# chibarobo2024.net
KiCad netlist of a schematic drawn in EAGLE
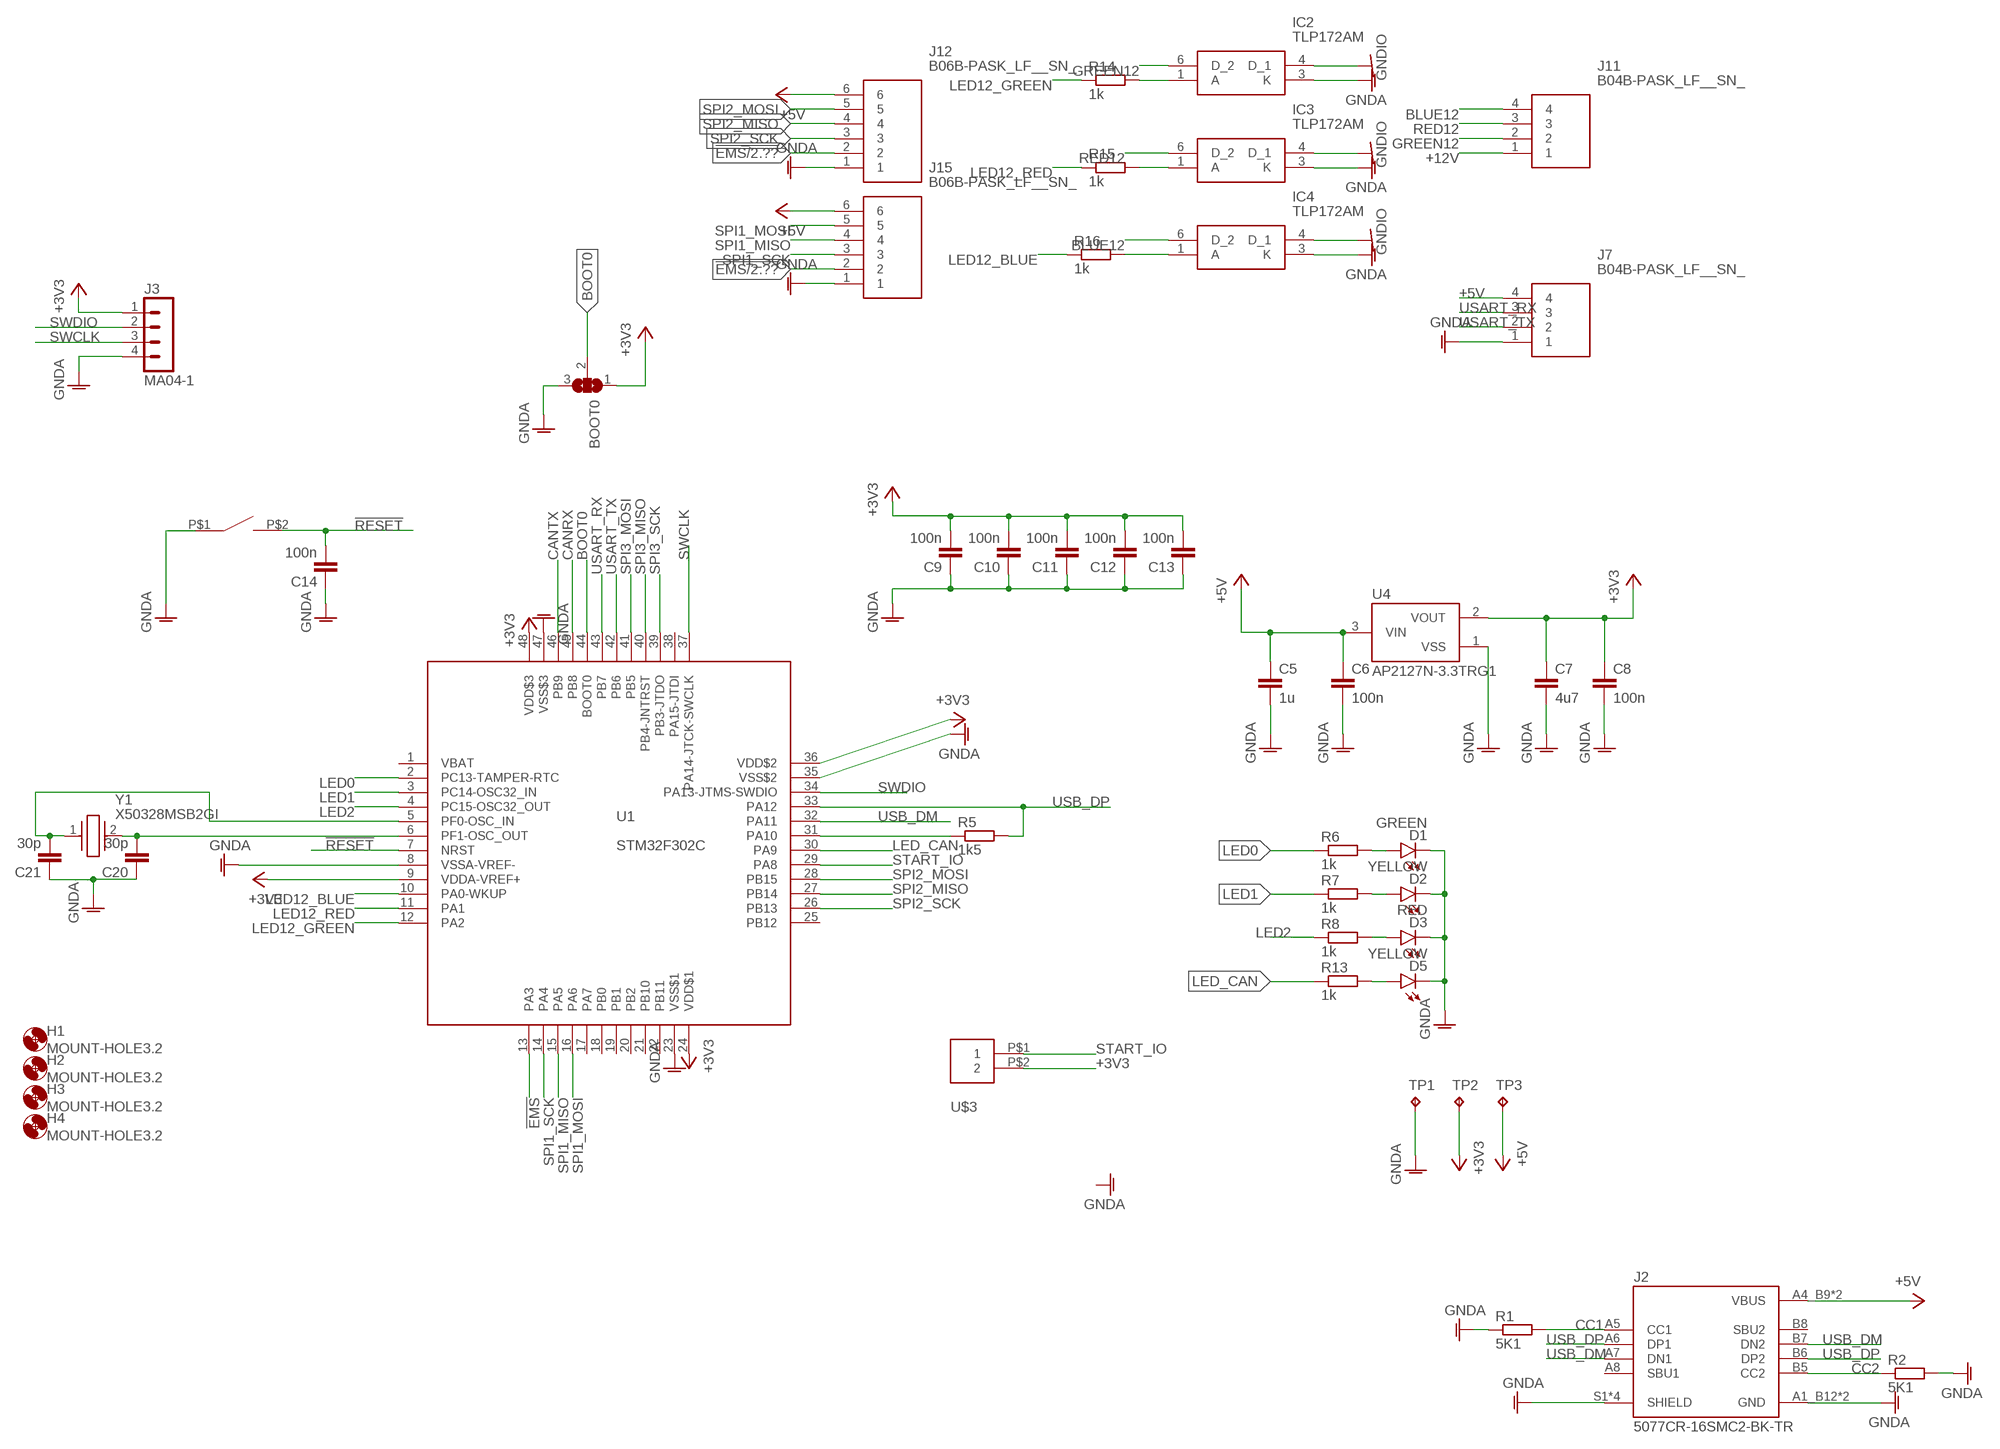
[diagram p0: schematic, sheet 1]
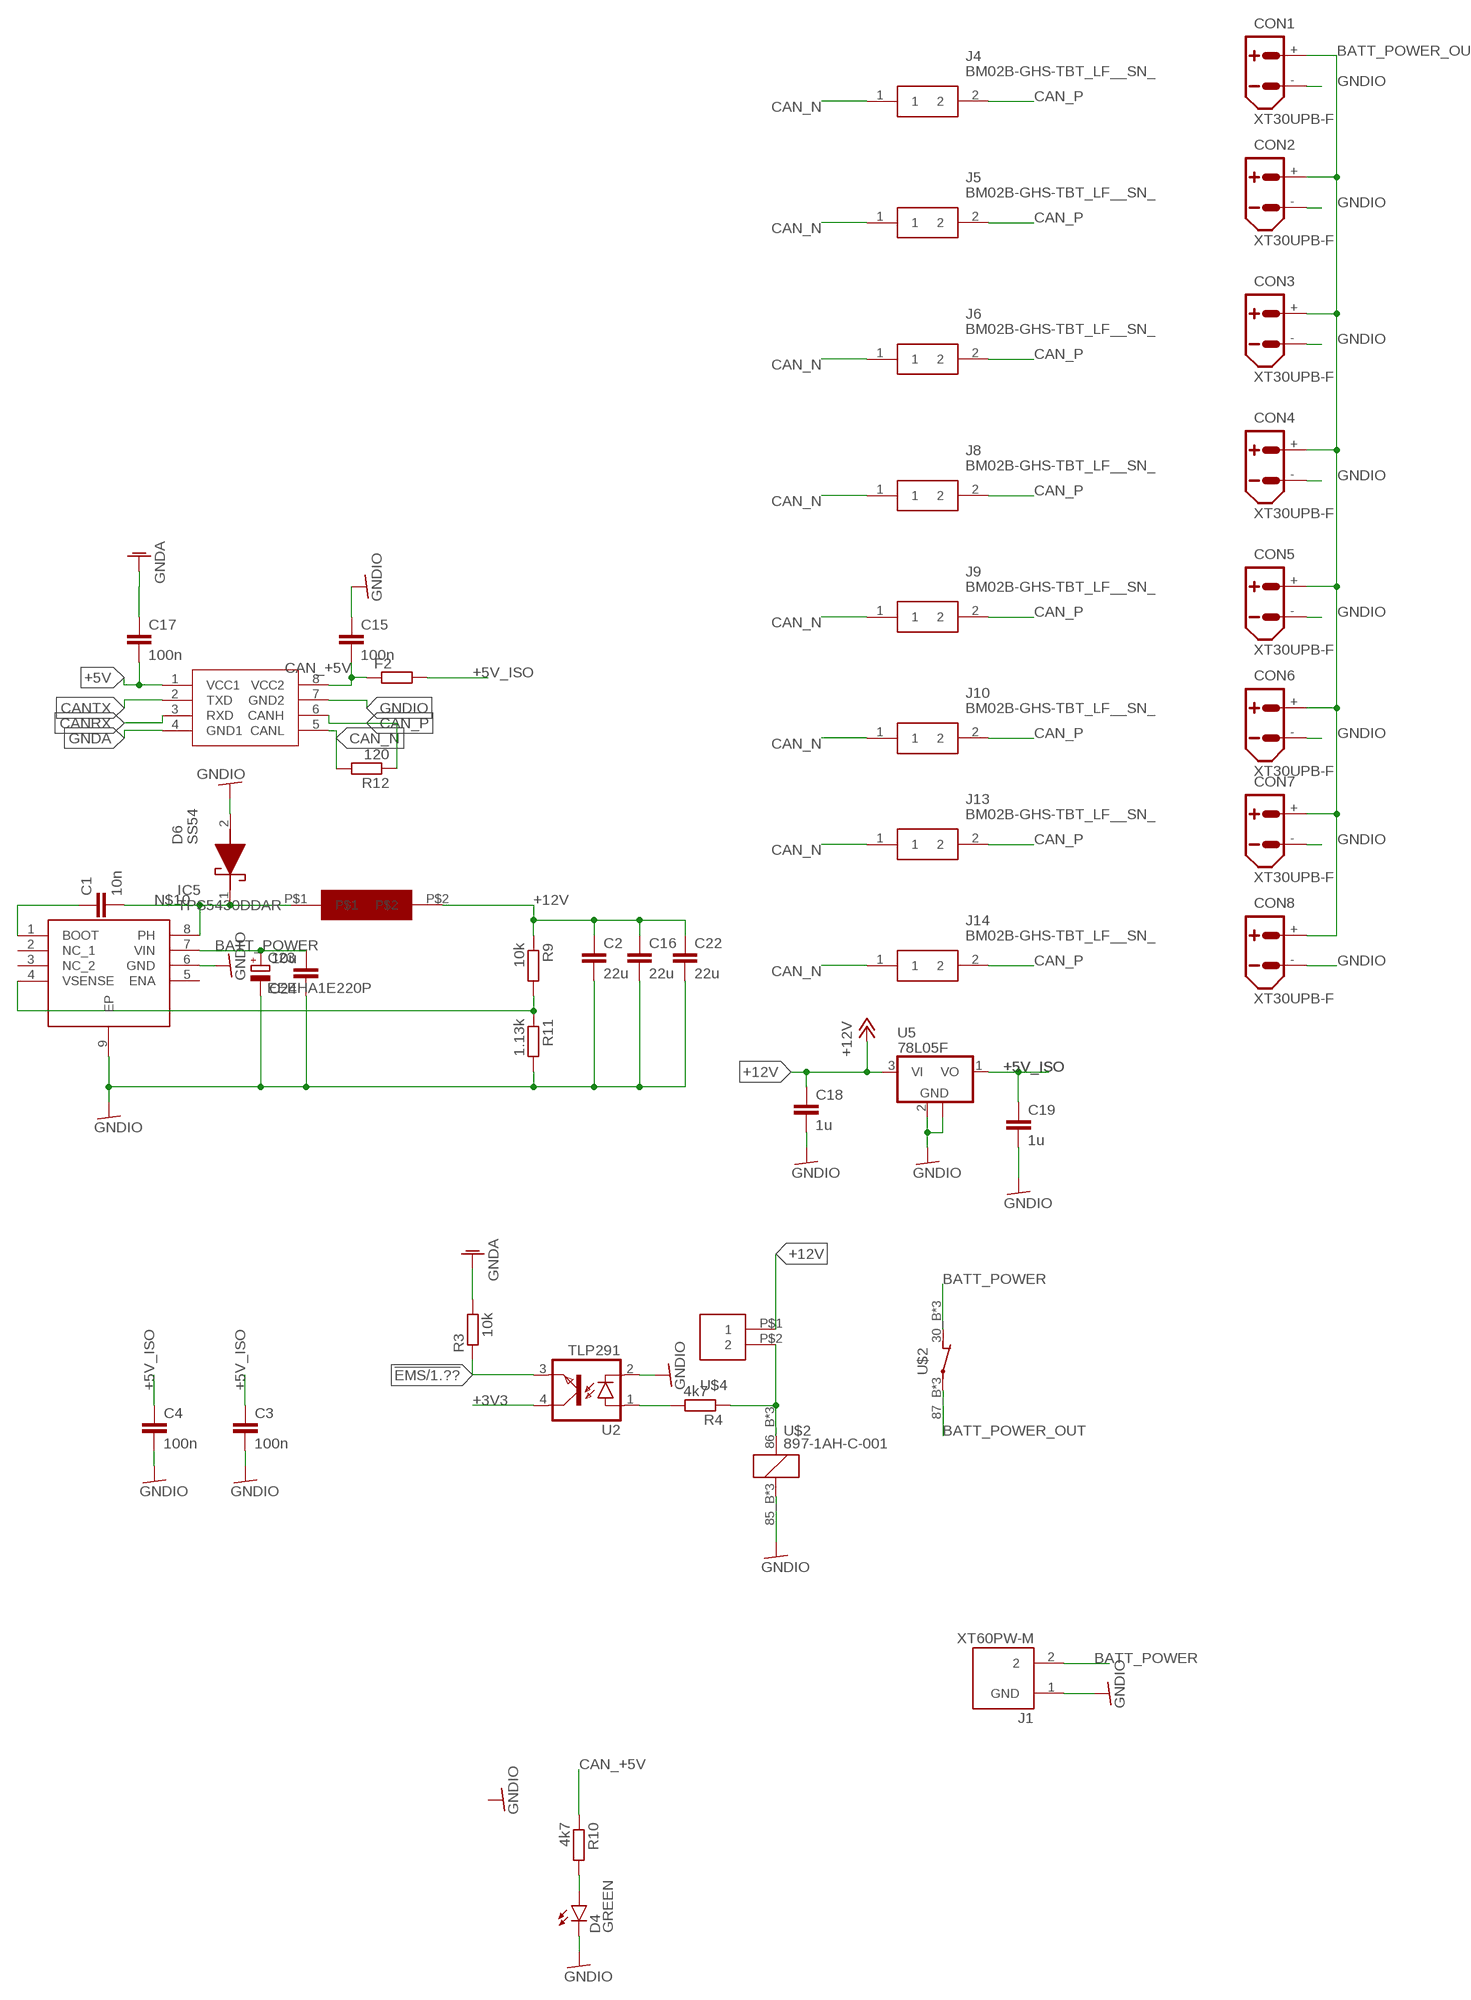
[diagram p1: schematic, sheet 2]

(export (version "E")
  (design (tool "Eeschema 10.0.6"))
  (components
    (comp (ref "BOOT0")
      (value "SJ2W")
      (footprint "eagle-import:SJ_2")
      (libsource (lib "eagle-import") (part "SJ2W"))
    )
    (comp (ref "C5")
      (value "1u")
      (footprint "eagle-import:C0603")
      (libsource (lib "eagle-import") (part "C-EUC0603"))
    )
    (comp (ref "C6")
      (value "100n")
      (footprint "eagle-import:C0603")
      (libsource (lib "eagle-import") (part "C-EUC0603"))
    )
    (comp (ref "C7")
      (value "4u7")
      (footprint "eagle-import:C0805")
      (libsource (lib "eagle-import") (part "C-EUC0805"))
    )
    (comp (ref "C8")
      (value "100n")
      (footprint "eagle-import:C0603")
      (libsource (lib "eagle-import") (part "C-EUC0603"))
    )
    (comp (ref "C9")
      (value "100n")
      (footprint "eagle-import:C0603")
      (libsource (lib "eagle-import") (part "C-EUC0603"))
    )
    (comp (ref "C10")
      (value "100n")
      (footprint "eagle-import:C0603")
      (libsource (lib "eagle-import") (part "C-EUC0603"))
    )
    (comp (ref "C11")
      (value "100n")
      (footprint "eagle-import:C0603")
      (libsource (lib "eagle-import") (part "C-EUC0603"))
    )
    (comp (ref "C12")
      (value "100n")
      (footprint "eagle-import:C0603")
      (libsource (lib "eagle-import") (part "C-EUC0603"))
    )
    (comp (ref "C13")
      (value "100n")
      (footprint "eagle-import:C0603")
      (libsource (lib "eagle-import") (part "C-EUC0603"))
    )
    (comp (ref "C14")
      (value "100n")
      (footprint "eagle-import:C0603")
      (libsource (lib "eagle-import") (part "C-EUC0603"))
    )
    (comp (ref "C20")
      (value "30p")
      (footprint "eagle-import:C0603")
      (libsource (lib "eagle-import") (part "C-EUC0603"))
    )
    (comp (ref "C21")
      (value "30p")
      (footprint "eagle-import:C0603")
      (libsource (lib "eagle-import") (part "C-EUC0603"))
    )
    (comp (ref "D1")
      (value "GREEN")
      (footprint "eagle-import:CHIPLED_0805")
      (libsource (lib "eagle-import") (part "LEDCHIPLED_0805"))
    )
    (comp (ref "D2")
      (value "YELLOW")
      (footprint "eagle-import:CHIPLED_0805")
      (libsource (lib "eagle-import") (part "LEDCHIPLED_0805"))
    )
    (comp (ref "D3")
      (value "RED")
      (footprint "eagle-import:CHIPLED_0805")
      (libsource (lib "eagle-import") (part "LEDCHIPLED_0805"))
    )
    (comp (ref "D5")
      (value "YELLOW")
      (footprint "eagle-import:CHIPLED_0805")
      (libsource (lib "eagle-import") (part "LEDCHIPLED_0805"))
    )
    (comp (ref "H1")
      (value "MOUNT-HOLE3.2")
      (footprint "eagle-import:3,2")
      (libsource (lib "eagle-import") (part "MOUNT-HOLE3.2"))
    )
    (comp (ref "H2")
      (value "MOUNT-HOLE3.2")
      (footprint "eagle-import:3,2")
      (libsource (lib "eagle-import") (part "MOUNT-HOLE3.2"))
    )
    (comp (ref "H3")
      (value "MOUNT-HOLE3.2")
      (footprint "eagle-import:3,2")
      (libsource (lib "eagle-import") (part "MOUNT-HOLE3.2"))
    )
    (comp (ref "H4")
      (value "MOUNT-HOLE3.2")
      (footprint "eagle-import:3,2")
      (libsource (lib "eagle-import") (part "MOUNT-HOLE3.2"))
    )
    (comp (ref "IC2")
      (value "TLP172AM")
      (footprint "eagle-import:11-4M1S")
      (libsource (lib "eagle-import") (part "TLP172AM"))
    )
    (comp (ref "IC3")
      (value "TLP172AM")
      (footprint "eagle-import:11-4M1S")
      (libsource (lib "eagle-import") (part "TLP172AM"))
    )
    (comp (ref "IC4")
      (value "TLP172AM")
      (footprint "eagle-import:11-4M1S")
      (libsource (lib "eagle-import") (part "TLP172AM"))
    )
    (comp (ref "J2")
      (value "5077CR-16SMC2-BK-TR")
      (footprint "eagle-import:NELTRON_5077CR-16SMC2-BK-TR")
      (fields (field (name "MF") "Neltron"))
      (libsource (lib "eagle-import") (part "5077CR-16SMC2-BK-TR"))
    )
    (comp (ref "J3")
      (value "MA04-1")
      (footprint "eagle-import:MA04-1")
      (libsource (lib "eagle-import") (part "MA04-1"))
    )
    (comp (ref "J7")
      (value "B04B-PASK_LF__SN_")
      (footprint "eagle-import:B04BPASKLFSN")
      (fields (field (name "ARROW_PART_NUMBER") "B04B-PASK(LF)(SN)"))
      (libsource (lib "eagle-import") (part "B04B-PASK_LF__SN_"))
    )
    (comp (ref "J11")
      (value "B04B-PASK_LF__SN_")
      (footprint "eagle-import:B04BPASKLFSN")
      (fields (field (name "ARROW_PART_NUMBER") "B04B-PASK(LF)(SN)"))
      (libsource (lib "eagle-import") (part "B04B-PASK_LF__SN_"))
    )
    (comp (ref "J12")
      (value "B06B-PASK_LF__SN_")
      (footprint "eagle-import:B06BPASKLFSN")
      (fields
        (field (name "ARROW_PART_NUMBER") "B06B-PASK(LF)(SN)")
        (field (name "MOUSER_PART_NUMBER") "306-B06BPASKLFSN")
      )
      (libsource (lib "eagle-import") (part "B06B-PASK_LF__SN_"))
    )
    (comp (ref "J15")
      (value "B06B-PASK_LF__SN_")
      (footprint "eagle-import:B06BPASKLFSN")
      (fields
        (field (name "ARROW_PART_NUMBER") "B06B-PASK(LF)(SN)")
        (field (name "MOUSER_PART_NUMBER") "306-B06BPASKLFSN")
      )
      (libsource (lib "eagle-import") (part "B06B-PASK_LF__SN_"))
    )
    (comp (ref "R1")
      (value "5K1")
      (footprint "eagle-import:R0603")
      (libsource (lib "eagle-import") (part "R-EU_R0603"))
    )
    (comp (ref "R2")
      (value "5K1")
      (footprint "eagle-import:R0603")
      (libsource (lib "eagle-import") (part "R-EU_R0603"))
    )
    (comp (ref "R5")
      (value "1k5")
      (footprint "eagle-import:R0603")
      (libsource (lib "eagle-import") (part "R-EU_R0603"))
    )
    (comp (ref "R6")
      (value "1k")
      (footprint "eagle-import:R0603")
      (libsource (lib "eagle-import") (part "R-EU_R0603"))
    )
    (comp (ref "R7")
      (value "1k")
      (footprint "eagle-import:R0603")
      (libsource (lib "eagle-import") (part "R-EU_R0603"))
    )
    (comp (ref "R8")
      (value "1k")
      (footprint "eagle-import:R0603")
      (libsource (lib "eagle-import") (part "R-EU_R0603"))
    )
    (comp (ref "R13")
      (value "1k")
      (footprint "eagle-import:R0603")
      (libsource (lib "eagle-import") (part "R-EU_R0603"))
    )
    (comp (ref "R14")
      (value "1k")
      (footprint "eagle-import:R0603")
      (libsource (lib "eagle-import") (part "R-EU_R0603"))
    )
    (comp (ref "R15")
      (value "1k")
      (footprint "eagle-import:R0603")
      (libsource (lib "eagle-import") (part "R-EU_R0603"))
    )
    (comp (ref "R16")
      (value "1k")
      (footprint "eagle-import:R0603")
      (libsource (lib "eagle-import") (part "R-EU_R0603"))
    )
    (comp (ref "S1")
      (value "SWITCH_TACTILETOP")
      (footprint "eagle-import:SWITCH_TACTILE_3X6")
      (libsource (lib "eagle-import") (part "SWITCH_TACTILETOP"))
    )
    (comp (ref "TP1")
      (value "TPB1,27")
      (footprint "eagle-import:B1,27")
      (libsource (lib "eagle-import") (part "TPB1,27"))
    )
    (comp (ref "TP2")
      (value "TPB1,27")
      (footprint "eagle-import:B1,27")
      (libsource (lib "eagle-import") (part "TPB1,27"))
    )
    (comp (ref "TP3")
      (value "TPB1,27")
      (footprint "eagle-import:B1,27")
      (libsource (lib "eagle-import") (part "TPB1,27"))
    )
    (comp (ref "U$3")
      (value "XH-2-STRAIGHT")
      (footprint "eagle-import:CON-XH-2-STRAIGHT")
      (libsource (lib "eagle-import") (part "XH-2-STRAIGHT"))
    )
    (comp (ref "U1")
      (value "STM32F302C")
      (footprint "eagle-import:LQFP48")
      (libsource (lib "eagle-import") (part "STM32F303C"))
    )
    (comp (ref "U4")
      (value "AP2127N-3.3TRG1")
      (footprint "eagle-import:SOT95P240X110-3")
      (libsource (lib "eagle-import") (part "XC6206"))
    )
    (comp (ref "Y1")
      (value "X50328MSB2GI")
      (footprint "eagle-import:RESC5032X135N")
      (libsource (lib "eagle-import") (part "X50328MSB2GI"))
    )
    (comp (ref "C1")
      (value "10n")
      (footprint "eagle-import:C0603")
      (libsource (lib "eagle-import") (part "rcl_334_C-EUC0603"))
    )
    (comp (ref "C2")
      (value "22u")
      (footprint "eagle-import:C0805")
      (libsource (lib "eagle-import") (part "rcl_334_C-EUC0805"))
    )
    (comp (ref "C3")
      (value "100n")
      (footprint "eagle-import:C0603")
      (libsource (lib "eagle-import") (part "rcl_334_C-EUC0603"))
    )
    (comp (ref "C4")
      (value "100n")
      (footprint "eagle-import:C0603")
      (libsource (lib "eagle-import") (part "rcl_334_C-EUC0603"))
    )
    (comp (ref "C15")
      (value "100n")
      (footprint "eagle-import:C0603")
      (libsource (lib "eagle-import") (part "rcl_334_C-EUC0603"))
    )
    (comp (ref "C16")
      (value "22u")
      (footprint "eagle-import:C0805")
      (libsource (lib "eagle-import") (part "rcl_334_C-EUC0805"))
    )
    (comp (ref "C17")
      (value "100n")
      (footprint "eagle-import:C0603")
      (libsource (lib "eagle-import") (part "rcl_334_C-EUC0603"))
    )
    (comp (ref "C18")
      (value "1u")
      (footprint "eagle-import:C0603")
      (libsource (lib "eagle-import") (part "C-EUC0603"))
    )
    (comp (ref "C19")
      (value "1u")
      (footprint "eagle-import:C0603")
      (libsource (lib "eagle-import") (part "C-EUC0603"))
    )
    (comp (ref "C22")
      (value "22u")
      (footprint "eagle-import:C0805")
      (libsource (lib "eagle-import") (part "rcl_334_C-EUC0805"))
    )
    (comp (ref "C23")
      (value "EEEHA1E220P")
      (footprint "eagle-import:153CLV-0605")
      (libsource (lib "eagle-import") (part "CPOL-EU153CLV-0605"))
    )
    (comp (ref "C24")
      (value "10u")
      (footprint "eagle-import:C1210")
      (libsource (lib "eagle-import") (part "rcl_334_C-EUC1210"))
    )
    (comp (ref "CON1")
      (value "XT30UPB-F")
      (footprint "eagle-import:XT30UPB-F")
      (libsource (lib "eagle-import") (part "XT30UPB-F"))
    )
    (comp (ref "CON2")
      (value "XT30UPB-F")
      (footprint "eagle-import:XT30UPB-F")
      (libsource (lib "eagle-import") (part "XT30UPB-F"))
    )
    (comp (ref "CON3")
      (value "XT30UPB-F")
      (footprint "eagle-import:XT30UPB-F")
      (libsource (lib "eagle-import") (part "XT30UPB-F"))
    )
    (comp (ref "CON4")
      (value "XT30UPB-F")
      (footprint "eagle-import:XT30UPB-F")
      (libsource (lib "eagle-import") (part "XT30UPB-F"))
    )
    (comp (ref "CON5")
      (value "XT30UPB-F")
      (footprint "eagle-import:XT30UPB-F")
      (libsource (lib "eagle-import") (part "XT30UPB-F"))
    )
    (comp (ref "CON6")
      (value "XT30UPB-F")
      (footprint "eagle-import:XT30UPB-F")
      (libsource (lib "eagle-import") (part "XT30UPB-F"))
    )
    (comp (ref "CON7")
      (value "XT30UPB-F")
      (footprint "eagle-import:XT30UPB-F")
      (libsource (lib "eagle-import") (part "XT30UPB-F"))
    )
    (comp (ref "CON8")
      (value "XT30UPB-F")
      (footprint "eagle-import:XT30UPB-F")
      (libsource (lib "eagle-import") (part "XT30UPB-F"))
    )
    (comp (ref "D4")
      (value "GREEN")
      (footprint "eagle-import:CHIPLED_0805")
      (libsource (lib "eagle-import") (part "LEDCHIPLED_0805"))
    )
    (comp (ref "D6")
      (value "SS54")
      (footprint "eagle-import:DIOM5126X245N")
      (libsource (lib "eagle-import") (part "SS54"))
    )
    (comp (ref "F2")
      (value "R-EU_R1206")
      (footprint "eagle-import:R1206")
      (libsource (lib "eagle-import") (part "R-EU_R1206"))
    )
    (comp (ref "IC5")
      (value "TPS5430DDAR")
      (footprint "eagle-import:SOIC127P600X170-9N")
      (libsource (lib "eagle-import") (part "TPS5430DDAR"))
    )
    (comp (ref "J1")
      (value "XT60PW-M")
      (footprint "eagle-import:AMASS_XT60PW-M")
      (fields (field (name "MF") "AMASS") (field (name "MP") "XT60PW-M "))
      (libsource (lib "eagle-import") (part "XT60PW-M"))
    )
    (comp (ref "J4")
      (value "BM02B-GHS-TBT_LF__SN_")
      (footprint "eagle-import:BM02B-GHS-TBT_1")
      (fields (field (name "MANUFACTURER_PART_NUMBER") "BM02B-GHS-TBT(LF)(SN)"))
      (libsource (lib "eagle-import") (part "BM02B-GHS-TBT_LF__SN_"))
    )
    (comp (ref "J5")
      (value "BM02B-GHS-TBT_LF__SN_")
      (footprint "eagle-import:BM02B-GHS-TBT_1")
      (fields (field (name "MANUFACTURER_PART_NUMBER") "BM02B-GHS-TBT(LF)(SN)"))
      (libsource (lib "eagle-import") (part "BM02B-GHS-TBT_LF__SN_"))
    )
    (comp (ref "J6")
      (value "BM02B-GHS-TBT_LF__SN_")
      (footprint "eagle-import:BM02B-GHS-TBT_1")
      (fields (field (name "MANUFACTURER_PART_NUMBER") "BM02B-GHS-TBT(LF)(SN)"))
      (libsource (lib "eagle-import") (part "BM02B-GHS-TBT_LF__SN_"))
    )
    (comp (ref "J8")
      (value "BM02B-GHS-TBT_LF__SN_")
      (footprint "eagle-import:BM02B-GHS-TBT_1")
      (fields (field (name "MANUFACTURER_PART_NUMBER") "BM02B-GHS-TBT(LF)(SN)"))
      (libsource (lib "eagle-import") (part "BM02B-GHS-TBT_LF__SN_"))
    )
    (comp (ref "J9")
      (value "BM02B-GHS-TBT_LF__SN_")
      (footprint "eagle-import:BM02B-GHS-TBT_1")
      (fields (field (name "MANUFACTURER_PART_NUMBER") "BM02B-GHS-TBT(LF)(SN)"))
      (libsource (lib "eagle-import") (part "BM02B-GHS-TBT_LF__SN_"))
    )
    (comp (ref "J10")
      (value "BM02B-GHS-TBT_LF__SN_")
      (footprint "eagle-import:BM02B-GHS-TBT_1")
      (fields (field (name "MANUFACTURER_PART_NUMBER") "BM02B-GHS-TBT(LF)(SN)"))
      (libsource (lib "eagle-import") (part "BM02B-GHS-TBT_LF__SN_"))
    )
    (comp (ref "J13")
      (value "BM02B-GHS-TBT_LF__SN_")
      (footprint "eagle-import:BM02B-GHS-TBT_1")
      (fields (field (name "MANUFACTURER_PART_NUMBER") "BM02B-GHS-TBT(LF)(SN)"))
      (libsource (lib "eagle-import") (part "BM02B-GHS-TBT_LF__SN_"))
    )
    (comp (ref "J14")
      (value "BM02B-GHS-TBT_LF__SN_")
      (footprint "eagle-import:BM02B-GHS-TBT_1")
      (fields (field (name "MANUFACTURER_PART_NUMBER") "BM02B-GHS-TBT(LF)(SN)"))
      (libsource (lib "eagle-import") (part "BM02B-GHS-TBT_LF__SN_"))
    )
    (comp (ref "R3")
      (value "10k")
      (footprint "eagle-import:R0603")
      (libsource (lib "eagle-import") (part "R-EU_R0603"))
    )
    (comp (ref "R4")
      (value "4k7")
      (footprint "eagle-import:R0603")
      (libsource (lib "eagle-import") (part "R-EU_R0603"))
    )
    (comp (ref "R9")
      (value "10k")
      (footprint "eagle-import:R0603")
      (libsource (lib "eagle-import") (part "rcl_334_R-EU_R0603"))
    )
    (comp (ref "R10")
      (value "4k7")
      (footprint "eagle-import:R0603")
      (libsource (lib "eagle-import") (part "R-EU_R0603"))
    )
    (comp (ref "R11")
      (value "1.13k")
      (footprint "eagle-import:R0603")
      (libsource (lib "eagle-import") (part "rcl_334_R-EU_R0603"))
    )
    (comp (ref "R12")
      (value "120")
      (footprint "eagle-import:R0603")
      (libsource (lib "eagle-import") (part "rcl_334_R-EU_R0603"))
    )
    (comp (ref "U$1")
      (value "CA-IS1044S")
      (footprint "eagle-import:SOIC8")
      (libsource (lib "eagle-import") (part "CA-IS1044S"))
    )
    (comp (ref "U$2")
      (value "897-1AH-C-001")
      (footprint "eagle-import:897-1AH-C-001")
      (libsource (lib "eagle-import") (part "897-1AH-C-001"))
    )
    (comp (ref "U$4")
      (value "XH-2-STRAIGHT")
      (footprint "eagle-import:CON-XH-2-STRAIGHT")
      (libsource (lib "eagle-import") (part "XH-2-STRAIGHT"))
    )
    (comp (ref "U$5")
      (value "INDUCTOR125_125")
      (footprint "eagle-import:INDUCTOR125_125")
      (libsource (lib "eagle-import") (part "INDUCTOR125_125"))
    )
    (comp (ref "U2")
      (value "TLP291")
      (footprint "eagle-import:MINI-FLAT-4")
      (libsource (lib "eagle-import") (part "TLP291"))
    )
    (comp (ref "U5")
      (value "78L05F")
      (footprint "eagle-import:SOT89")
      (libsource (lib "eagle-import") (part "78LF05"))
    )
  )
  (nets
    (net (code "1") (name "+3V3") (class "Default")
      (node (ref "BOOT0") (pin "1") (pinfunction "1_1") (pintype "passive"))
      (node (ref "C10") (pin "2") (pinfunction "2_2") (pintype "passive"))
      (node (ref "C11") (pin "2") (pinfunction "2_2") (pintype "passive"))
      (node (ref "C12") (pin "2") (pinfunction "2_2") (pintype "passive"))
      (node (ref "C13") (pin "2") (pinfunction "2_2") (pintype "passive"))
      (node (ref "C7") (pin "1") (pinfunction "1_1") (pintype "passive"))
      (node (ref "C8") (pin "1") (pinfunction "1_1") (pintype "passive"))
      (node (ref "C9") (pin "2") (pinfunction "2_2") (pintype "passive"))
      (node (ref "J3") (pin "1") (pinfunction "1_1") (pintype "passive"))
      (node (ref "TP2") (pin "TP") (pinfunction "TP_TP") (pintype "input"))
      (node (ref "U$3") (pin "P$2") (pinfunction "2_P$2") (pintype "bidirectional"))
      (node (ref "U1") (pin "24") (pinfunction "VDD$1_24") (pintype "passive"))
      (node (ref "U1") (pin "36") (pinfunction "VDD$2_36") (pintype "passive"))
      (node (ref "U1") (pin "48") (pinfunction "VDD$3_48") (pintype "passive"))
      (node (ref "U1") (pin "9") (pinfunction "VDDA-VREF+_9") (pintype "bidirectional"))
      (node (ref "U2") (pin "4") (pinfunction "COL_4") (pintype "passive"))
      (node (ref "U4") (pin "2") (pinfunction "VOUT_2") (pintype "bidirectional"))
    )
    (net (code "2") (name "+5V") (class "Default")
      (node (ref "C17") (pin "2") (pinfunction "2_2") (pintype "passive"))
      (node (ref "C5") (pin "1") (pinfunction "1_1") (pintype "passive"))
      (node (ref "C6") (pin "1") (pinfunction "1_1") (pintype "passive"))
      (node (ref "J12") (pin "6") (pinfunction "6_6") (pintype "bidirectional"))
      (node (ref "J15") (pin "6") (pinfunction "6_6") (pintype "bidirectional"))
      (node (ref "J2") (pin "A4_B9") (pinfunction "VBUS_A4_B9") (pintype "power_in"))
      (node (ref "J2") (pin "B4_A9") (pinfunction "VBUS_B4_A9") (pintype "power_in"))
      (node (ref "J7") (pin "4") (pinfunction "4_4") (pintype "bidirectional"))
      (node (ref "TP3") (pin "TP") (pinfunction "TP_TP") (pintype "input"))
      (node (ref "U$1") (pin "1") (pinfunction "VCC1_1") (pintype "bidirectional"))
      (node (ref "U4") (pin "3") (pinfunction "VIN_3") (pintype "bidirectional"))
    )
    (net (code "3") (name "+5V_ISO") (class "Default")
      (node (ref "C19") (pin "1") (pinfunction "1_1") (pintype "passive"))
      (node (ref "C3") (pin "1") (pinfunction "1_1") (pintype "passive"))
      (node (ref "C4") (pin "1") (pinfunction "1_1") (pintype "passive"))
      (node (ref "F2") (pin "2") (pinfunction "2_2") (pintype "passive"))
      (node (ref "U5") (pin "1") (pinfunction "VO_1") (pintype "passive"))
    )
    (net (code "4") (name "+12V") (class "Default")
      (node (ref "C16") (pin "1") (pinfunction "1_1") (pintype "passive"))
      (node (ref "C18") (pin "1") (pinfunction "1_1") (pintype "passive"))
      (node (ref "C2") (pin "1") (pinfunction "1_1") (pintype "passive"))
      (node (ref "C22") (pin "1") (pinfunction "1_1") (pintype "passive"))
      (node (ref "J11") (pin "1") (pinfunction "1_1") (pintype "bidirectional"))
      (node (ref "R9") (pin "1") (pinfunction "1_1") (pintype "passive"))
      (node (ref "U$4") (pin "P$1") (pinfunction "1_P$1") (pintype "bidirectional"))
      (node (ref "U$5") (pin "P$2") (pinfunction "P$2_P$2") (pintype "bidirectional"))
      (node (ref "U5") (pin "3") (pinfunction "VI_3") (pintype "input"))
    )
    (net (code "5") (name "BATT_POWER") (class "Default")
      (node (ref "C23") (pin "+") (pinfunction "+_+") (pintype "passive"))
      (node (ref "C24") (pin "2") (pinfunction "2_2") (pintype "passive"))
      (node (ref "IC5") (pin "7") (pinfunction "VIN_7") (pintype "bidirectional"))
      (node (ref "J1") (pin "2") (pinfunction "2_2") (pintype "passive"))
      (node (ref "U$2") (pin "30_B") (pinfunction "O_30_B") (pintype "passive"))
      (node (ref "U$2") (pin "30_T") (pinfunction "O_30_T") (pintype "passive"))
      (node (ref "U$2") (pin "P$3") (pinfunction "O_P$3") (pintype "passive"))
    )
    (net (code "6") (name "BATT_POWER_OUT") (class "Default")
      (node (ref "CON1") (pin "+") (pinfunction "+_+") (pintype "power_in"))
      (node (ref "CON2") (pin "+") (pinfunction "+_+") (pintype "power_in"))
      (node (ref "CON3") (pin "+") (pinfunction "+_+") (pintype "power_in"))
      (node (ref "CON4") (pin "+") (pinfunction "+_+") (pintype "power_in"))
      (node (ref "CON5") (pin "+") (pinfunction "+_+") (pintype "power_in"))
      (node (ref "CON6") (pin "+") (pinfunction "+_+") (pintype "power_in"))
      (node (ref "CON7") (pin "+") (pinfunction "+_+") (pintype "power_in"))
      (node (ref "CON8") (pin "+") (pinfunction "+_+") (pintype "power_in"))
      (node (ref "U$2") (pin "87_B") (pinfunction "P_87_B") (pintype "passive"))
      (node (ref "U$2") (pin "87_T") (pinfunction "P_87_T") (pintype "passive"))
      (node (ref "U$2") (pin "P$1") (pinfunction "P_P$1") (pintype "passive"))
    )
    (net (code "7") (name "BLUE12") (class "Default")
      (node (ref "IC4") (pin "6") (pinfunction "D_2_6") (pintype "bidirectional"))
      (node (ref "J11") (pin "4") (pinfunction "4_4") (pintype "bidirectional"))
    )
    (net (code "8") (name "BOOT0") (class "Default")
      (node (ref "BOOT0") (pin "2") (pinfunction "2_2") (pintype "passive"))
      (node (ref "U1") (pin "44") (pinfunction "BOOT0_44") (pintype "input"))
    )
    (net (code "9") (name "CANRX") (class "Default")
      (node (ref "U$1") (pin "3") (pinfunction "RXD_3") (pintype "bidirectional"))
      (node (ref "U1") (pin "45") (pinfunction "PB8_45") (pintype "bidirectional"))
    )
    (net (code "10") (name "CANTX") (class "Default")
      (node (ref "U$1") (pin "2") (pinfunction "TXD_2") (pintype "bidirectional"))
      (node (ref "U1") (pin "46") (pinfunction "PB9_46") (pintype "bidirectional"))
    )
    (net (code "11") (name "CAN_+5V") (class "Default")
      (node (ref "C15") (pin "2") (pinfunction "2_2") (pintype "passive"))
      (node (ref "F2") (pin "1") (pinfunction "1_1") (pintype "passive"))
      (node (ref "R10") (pin "1") (pinfunction "1_1") (pintype "passive"))
      (node (ref "U$1") (pin "8") (pinfunction "VCC2_8") (pintype "bidirectional"))
    )
    (net (code "12") (name "CAN_N") (class "Default")
      (node (ref "J10") (pin "1") (pinfunction "1_1") (pintype "bidirectional"))
      (node (ref "J13") (pin "1") (pinfunction "1_1") (pintype "bidirectional"))
      (node (ref "J14") (pin "1") (pinfunction "1_1") (pintype "bidirectional"))
      (node (ref "J4") (pin "1") (pinfunction "1_1") (pintype "bidirectional"))
      (node (ref "J5") (pin "1") (pinfunction "1_1") (pintype "bidirectional"))
      (node (ref "J6") (pin "1") (pinfunction "1_1") (pintype "bidirectional"))
      (node (ref "J8") (pin "1") (pinfunction "1_1") (pintype "bidirectional"))
      (node (ref "J9") (pin "1") (pinfunction "1_1") (pintype "bidirectional"))
      (node (ref "R12") (pin "2") (pinfunction "2_2") (pintype "passive"))
      (node (ref "U$1") (pin "5") (pinfunction "CANL_5") (pintype "bidirectional"))
    )
    (net (code "13") (name "CAN_P") (class "Default")
      (node (ref "J10") (pin "2") (pinfunction "2_2") (pintype "bidirectional"))
      (node (ref "J13") (pin "2") (pinfunction "2_2") (pintype "bidirectional"))
      (node (ref "J14") (pin "2") (pinfunction "2_2") (pintype "bidirectional"))
      (node (ref "J4") (pin "2") (pinfunction "2_2") (pintype "bidirectional"))
      (node (ref "J5") (pin "2") (pinfunction "2_2") (pintype "bidirectional"))
      (node (ref "J6") (pin "2") (pinfunction "2_2") (pintype "bidirectional"))
      (node (ref "J8") (pin "2") (pinfunction "2_2") (pintype "bidirectional"))
      (node (ref "J9") (pin "2") (pinfunction "2_2") (pintype "bidirectional"))
      (node (ref "R12") (pin "1") (pinfunction "1_1") (pintype "passive"))
      (node (ref "U$1") (pin "6") (pinfunction "CANH_6") (pintype "bidirectional"))
    )
    (net (code "14") (name "CC1") (class "Default")
      (node (ref "J2") (pin "A5") (pinfunction "CC1_A5") (pintype "passive"))
      (node (ref "R1") (pin "2") (pinfunction "2_2") (pintype "passive"))
    )
    (net (code "15") (name "CC2") (class "Default")
      (node (ref "J2") (pin "B5") (pinfunction "CC2_B5") (pintype "passive"))
      (node (ref "R2") (pin "1") (pinfunction "1_1") (pintype "passive"))
    )
    (net (code "16") (name "GNDA") (class "Default")
      (node (ref "BOOT0") (pin "3") (pinfunction "3_3") (pintype "passive"))
      (node (ref "C10") (pin "1") (pinfunction "1_1") (pintype "passive"))
      (node (ref "C11") (pin "1") (pinfunction "1_1") (pintype "passive"))
      (node (ref "C12") (pin "1") (pinfunction "1_1") (pintype "passive"))
      (node (ref "C13") (pin "1") (pinfunction "1_1") (pintype "passive"))
      (node (ref "C14") (pin "1") (pinfunction "1_1") (pintype "passive"))
      (node (ref "C17") (pin "1") (pinfunction "1_1") (pintype "passive"))
      (node (ref "C20") (pin "1") (pinfunction "1_1") (pintype "passive"))
      (node (ref "C21") (pin "1") (pinfunction "1_1") (pintype "passive"))
      (node (ref "C5") (pin "2") (pinfunction "2_2") (pintype "passive"))
      (node (ref "C6") (pin "2") (pinfunction "2_2") (pintype "passive"))
      (node (ref "C7") (pin "2") (pinfunction "2_2") (pintype "passive"))
      (node (ref "C8") (pin "2") (pinfunction "2_2") (pintype "passive"))
      (node (ref "C9") (pin "1") (pinfunction "1_1") (pintype "passive"))
      (node (ref "D1") (pin "C") (pinfunction "C_C") (pintype "passive"))
      (node (ref "D2") (pin "C") (pinfunction "C_C") (pintype "passive"))
      (node (ref "D3") (pin "C") (pinfunction "C_C") (pintype "passive"))
      (node (ref "D5") (pin "C") (pinfunction "C_C") (pintype "passive"))
      (node (ref "IC2") (pin "3") (pinfunction "K_3") (pintype "bidirectional"))
      (node (ref "IC3") (pin "3") (pinfunction "K_3") (pintype "bidirectional"))
      (node (ref "IC4") (pin "3") (pinfunction "K_3") (pintype "bidirectional"))
      (node (ref "J12") (pin "1") (pinfunction "1_1") (pintype "bidirectional"))
      (node (ref "J15") (pin "1") (pinfunction "1_1") (pintype "bidirectional"))
      (node (ref "J2") (pin "A1_B12") (pinfunction "GND_A1_B12") (pintype "power_in"))
      (node (ref "J2") (pin "B1_A12") (pinfunction "GND_B1_A12") (pintype "power_in"))
      (node (ref "J2") (pin "S1") (pinfunction "SHIELD_S1") (pintype "passive"))
      (node (ref "J2") (pin "S2") (pinfunction "SHIELD_S2") (pintype "passive"))
      (node (ref "J2") (pin "S3") (pinfunction "SHIELD_S3") (pintype "passive"))
      (node (ref "J2") (pin "S4") (pinfunction "SHIELD_S4") (pintype "passive"))
      (node (ref "J3") (pin "4") (pinfunction "4_4") (pintype "passive"))
      (node (ref "J7") (pin "1") (pinfunction "1_1") (pintype "bidirectional"))
      (node (ref "R1") (pin "1") (pinfunction "1_1") (pintype "passive"))
      (node (ref "R2") (pin "2") (pinfunction "2_2") (pintype "passive"))
      (node (ref "R3") (pin "2") (pinfunction "2_2") (pintype "passive"))
      (node (ref "S1") (pin "P$1") (pinfunction "1_P$1") (pintype "bidirectional"))
      (node (ref "TP1") (pin "TP") (pinfunction "TP_TP") (pintype "input"))
      (node (ref "U$1") (pin "4") (pinfunction "GND1_4") (pintype "bidirectional"))
      (node (ref "U1") (pin "23") (pinfunction "VSS$1_23") (pintype "passive"))
      (node (ref "U1") (pin "35") (pinfunction "VSS$2_35") (pintype "passive"))
      (node (ref "U1") (pin "47") (pinfunction "VSS$3_47") (pintype "passive"))
      (node (ref "U1") (pin "8") (pinfunction "VSSA-VREF-_8") (pintype "bidirectional"))
      (node (ref "U4") (pin "1") (pinfunction "VSS_1") (pintype "bidirectional"))
    )
    (net (code "17") (name "GNDIO") (class "Default")
      (node (ref "C15") (pin "1") (pinfunction "1_1") (pintype "passive"))
      (node (ref "C16") (pin "2") (pinfunction "2_2") (pintype "passive"))
      (node (ref "C18") (pin "2") (pinfunction "2_2") (pintype "passive"))
      (node (ref "C19") (pin "2") (pinfunction "2_2") (pintype "passive"))
      (node (ref "C2") (pin "2") (pinfunction "2_2") (pintype "passive"))
      (node (ref "C22") (pin "2") (pinfunction "2_2") (pintype "passive"))
      (node (ref "C23") (pin "-") (pinfunction "-_-") (pintype "passive"))
      (node (ref "C24") (pin "1") (pinfunction "1_1") (pintype "passive"))
      (node (ref "C3") (pin "2") (pinfunction "2_2") (pintype "passive"))
      (node (ref "C4") (pin "2") (pinfunction "2_2") (pintype "passive"))
      (node (ref "CON1") (pin "-") (pinfunction "-_-") (pintype "power_in"))
      (node (ref "CON2") (pin "-") (pinfunction "-_-") (pintype "power_in"))
      (node (ref "CON3") (pin "-") (pinfunction "-_-") (pintype "power_in"))
      (node (ref "CON4") (pin "-") (pinfunction "-_-") (pintype "power_in"))
      (node (ref "CON5") (pin "-") (pinfunction "-_-") (pintype "power_in"))
      (node (ref "CON6") (pin "-") (pinfunction "-_-") (pintype "power_in"))
      (node (ref "CON7") (pin "-") (pinfunction "-_-") (pintype "power_in"))
      (node (ref "CON8") (pin "-") (pinfunction "-_-") (pintype "power_in"))
      (node (ref "D4") (pin "C") (pinfunction "C_C") (pintype "passive"))
      (node (ref "D6") (pin "2") (pinfunction "A_2") (pintype "bidirectional"))
      (node (ref "IC2") (pin "4") (pinfunction "D_1_4") (pintype "bidirectional"))
      (node (ref "IC3") (pin "4") (pinfunction "D_1_4") (pintype "bidirectional"))
      (node (ref "IC4") (pin "4") (pinfunction "D_1_4") (pintype "bidirectional"))
      (node (ref "IC5") (pin "6") (pinfunction "GND_6") (pintype "bidirectional"))
      (node (ref "IC5") (pin "9") (pinfunction "EP_9") (pintype "bidirectional"))
      (node (ref "J1") (pin "1") (pinfunction "GND_1") (pintype "passive"))
      (node (ref "R11") (pin "2") (pinfunction "2_2") (pintype "passive"))
      (node (ref "U$1") (pin "7") (pinfunction "GND2_7") (pintype "bidirectional"))
      (node (ref "U$2") (pin "85_B") (pinfunction "2_85_B") (pintype "passive"))
      (node (ref "U$2") (pin "85_T") (pinfunction "2_85_T") (pintype "passive"))
      (node (ref "U$2") (pin "P$2") (pinfunction "2_P$2") (pintype "passive"))
      (node (ref "U2") (pin "2") (pinfunction "C_2") (pintype "passive"))
      (node (ref "U5") (pin "2") (pinfunction "GND_2") (pintype "passive"))
      (node (ref "U5") (pin "2@1") (pinfunction "GND_2@1") (pintype "passive"))
    )
    (net (code "18") (name "GREEN12") (class "Default")
      (node (ref "IC2") (pin "6") (pinfunction "D_2_6") (pintype "bidirectional"))
      (node (ref "J11") (pin "2") (pinfunction "2_2") (pintype "bidirectional"))
    )
    (net (code "19") (name "LED0") (class "Default")
      (node (ref "R6") (pin "1") (pinfunction "1_1") (pintype "passive"))
      (node (ref "U1") (pin "2") (pinfunction "PC13-TAMPER-RTC_2") (pintype "bidirectional"))
    )
    (net (code "20") (name "LED1") (class "Default")
      (node (ref "R7") (pin "1") (pinfunction "1_1") (pintype "passive"))
      (node (ref "U1") (pin "3") (pinfunction "PC14-OSC32_IN_3") (pintype "bidirectional"))
    )
    (net (code "21") (name "LED2") (class "Default")
      (node (ref "R8") (pin "1") (pinfunction "1_1") (pintype "passive"))
      (node (ref "U1") (pin "4") (pinfunction "PC15-OSC32_OUT_4") (pintype "bidirectional"))
    )
    (net (code "22") (name "LED12_BLUE") (class "Default")
      (node (ref "R16") (pin "1") (pinfunction "1_1") (pintype "passive"))
      (node (ref "U1") (pin "10") (pinfunction "PA0-WKUP_10") (pintype "bidirectional"))
    )
    (net (code "23") (name "LED12_GREEN") (class "Default")
      (node (ref "R14") (pin "1") (pinfunction "1_1") (pintype "passive"))
      (node (ref "U1") (pin "12") (pinfunction "PA2_12") (pintype "bidirectional"))
    )
    (net (code "24") (name "LED12_RED") (class "Default")
      (node (ref "R15") (pin "1") (pinfunction "1_1") (pintype "passive"))
      (node (ref "U1") (pin "11") (pinfunction "PA1_11") (pintype "bidirectional"))
    )
    (net (code "25") (name "LED_CAN") (class "Default")
      (node (ref "R13") (pin "1") (pinfunction "1_1") (pintype "passive"))
      (node (ref "U1") (pin "30") (pinfunction "PA9_30") (pintype "bidirectional"))
    )
    (net (code "26") (name "N$10") (class "Default")
      (node (ref "C1") (pin "2") (pinfunction "2_2") (pintype "passive"))
      (node (ref "D6") (pin "1") (pinfunction "K_1") (pintype "bidirectional"))
      (node (ref "IC5") (pin "8") (pinfunction "PH_8") (pintype "bidirectional"))
      (node (ref "U$5") (pin "P$1") (pinfunction "P$1_P$1") (pintype "bidirectional"))
    )
    (net (code "27") (name "Net-(D1-PadA)") (class "Default")
      (node (ref "D1") (pin "A") (pinfunction "A_A") (pintype "passive"))
      (node (ref "R6") (pin "2") (pinfunction "2_2") (pintype "passive"))
    )
    (net (code "28") (name "Net-(D2-PadA)") (class "Default")
      (node (ref "D2") (pin "A") (pinfunction "A_A") (pintype "passive"))
      (node (ref "R7") (pin "2") (pinfunction "2_2") (pintype "passive"))
    )
    (net (code "29") (name "Net-(D3-PadA)") (class "Default")
      (node (ref "D3") (pin "A") (pinfunction "A_A") (pintype "passive"))
      (node (ref "R8") (pin "2") (pinfunction "2_2") (pintype "passive"))
    )
    (net (code "30") (name "Net-(D4-PadA)") (class "Default")
      (node (ref "D4") (pin "A") (pinfunction "A_A") (pintype "passive"))
      (node (ref "R10") (pin "2") (pinfunction "2_2") (pintype "passive"))
    )
    (net (code "31") (name "Net-(D5-PadA)") (class "Default")
      (node (ref "D5") (pin "A") (pinfunction "A_A") (pintype "passive"))
      (node (ref "R13") (pin "2") (pinfunction "2_2") (pintype "passive"))
    )
    (net (code "32") (name "Net-(IC2-A)") (class "Default")
      (node (ref "IC2") (pin "1") (pinfunction "A_1") (pintype "bidirectional"))
      (node (ref "R14") (pin "2") (pinfunction "2_2") (pintype "passive"))
    )
    (net (code "33") (name "Net-(IC3-A)") (class "Default")
      (node (ref "IC3") (pin "1") (pinfunction "A_1") (pintype "bidirectional"))
      (node (ref "R15") (pin "2") (pinfunction "2_2") (pintype "passive"))
    )
    (net (code "34") (name "Net-(IC4-A)") (class "Default")
      (node (ref "IC4") (pin "1") (pinfunction "A_1") (pintype "bidirectional"))
      (node (ref "R16") (pin "2") (pinfunction "2_2") (pintype "passive"))
    )
    (net (code "35") (name "Net-(IC5-BOOT)") (class "Default")
      (node (ref "C1") (pin "1") (pinfunction "1_1") (pintype "passive"))
      (node (ref "IC5") (pin "1") (pinfunction "BOOT_1") (pintype "bidirectional"))
    )
    (net (code "36") (name "Net-(IC5-VSENSE)") (class "Default")
      (node (ref "IC5") (pin "4") (pinfunction "VSENSE_4") (pintype "bidirectional"))
      (node (ref "R11") (pin "1") (pinfunction "1_1") (pintype "passive"))
      (node (ref "R9") (pin "2") (pinfunction "2_2") (pintype "passive"))
    )
    (net (code "37") (name "Net-(U$4-2)") (class "Default")
      (node (ref "R4") (pin "1") (pinfunction "1_1") (pintype "passive"))
      (node (ref "U$2") (pin "86_B") (pinfunction "1_86_B") (pintype "passive"))
      (node (ref "U$2") (pin "86_T") (pinfunction "1_86_T") (pintype "passive"))
      (node (ref "U$2") (pin "P$4") (pinfunction "1_P$4") (pintype "passive"))
      (node (ref "U$4") (pin "P$2") (pinfunction "2_P$2") (pintype "bidirectional"))
    )
    (net (code "38") (name "Net-(U1-PA10)") (class "Default")
      (node (ref "R5") (pin "1") (pinfunction "1_1") (pintype "passive"))
      (node (ref "U1") (pin "31") (pinfunction "PA10_31") (pintype "bidirectional"))
    )
    (net (code "39") (name "Net-(U1-PF0-OSC_IN)") (class "Default")
      (node (ref "C21") (pin "2") (pinfunction "2_2") (pintype "passive"))
      (node (ref "U1") (pin "5") (pinfunction "PF0-OSC_IN_5") (pintype "input"))
      (node (ref "Y1") (pin "1") (pinfunction "1_1") (pintype "bidirectional"))
    )
    (net (code "40") (name "Net-(U1-PF1-OSC_OUT)") (class "Default")
      (node (ref "C20") (pin "2") (pinfunction "2_2") (pintype "passive"))
      (node (ref "U1") (pin "6") (pinfunction "PF1-OSC_OUT_6") (pintype "output"))
      (node (ref "Y1") (pin "2") (pinfunction "2_2") (pintype "bidirectional"))
    )
    (net (code "41") (name "Net-(U2-A)") (class "Default")
      (node (ref "R4") (pin "2") (pinfunction "2_2") (pintype "passive"))
      (node (ref "U2") (pin "1") (pinfunction "A_1") (pintype "passive"))
    )
    (net (code "42") (name "RED12") (class "Default")
      (node (ref "IC3") (pin "6") (pinfunction "D_2_6") (pintype "bidirectional"))
      (node (ref "J11") (pin "3") (pinfunction "3_3") (pintype "bidirectional"))
    )
    (net (code "43") (name "SPI1_MISO") (class "Default")
      (node (ref "J15") (pin "4") (pinfunction "4_4") (pintype "bidirectional"))
      (node (ref "U1") (pin "15") (pinfunction "PA5_15") (pintype "bidirectional"))
    )
    (net (code "44") (name "SPI1_MOSI") (class "Default")
      (node (ref "J15") (pin "5") (pinfunction "5_5") (pintype "bidirectional"))
      (node (ref "U1") (pin "16") (pinfunction "PA6_16") (pintype "bidirectional"))
    )
    (net (code "45") (name "SPI1_SCK") (class "Default")
      (node (ref "J15") (pin "3") (pinfunction "3_3") (pintype "bidirectional"))
      (node (ref "U1") (pin "14") (pinfunction "PA4_14") (pintype "bidirectional"))
    )
    (net (code "46") (name "SPI2_MISO") (class "Default")
      (node (ref "J12") (pin "4") (pinfunction "4_4") (pintype "bidirectional"))
      (node (ref "U1") (pin "27") (pinfunction "PB14_27") (pintype "bidirectional"))
    )
    (net (code "47") (name "SPI2_MOSI") (class "Default")
      (node (ref "J12") (pin "5") (pinfunction "5_5") (pintype "bidirectional"))
      (node (ref "U1") (pin "28") (pinfunction "PB15_28") (pintype "bidirectional"))
    )
    (net (code "48") (name "SPI2_SCK") (class "Default")
      (node (ref "J12") (pin "3") (pinfunction "3_3") (pintype "bidirectional"))
      (node (ref "U1") (pin "26") (pinfunction "PB13_26") (pintype "bidirectional"))
    )
    (net (code "49") (name "SPI3_MISO") (class "Default")
      (node (ref "U1") (pin "40") (pinfunction "PB4-JNTRST_40") (pintype "bidirectional"))
    )
    (net (code "50") (name "SPI3_MOSI") (class "Default")
      (node (ref "U1") (pin "41") (pinfunction "PB5_41") (pintype "bidirectional"))
    )
    (net (code "51") (name "SPI3_SCK") (class "Default")
      (node (ref "U1") (pin "39") (pinfunction "PB3-JTDO_39") (pintype "bidirectional"))
    )
    (net (code "52") (name "START_IO") (class "Default")
      (node (ref "U$3") (pin "P$1") (pinfunction "1_P$1") (pintype "bidirectional"))
      (node (ref "U1") (pin "29") (pinfunction "PA8_29") (pintype "bidirectional"))
    )
    (net (code "53") (name "SWCLK") (class "Default")
      (node (ref "J3") (pin "3") (pinfunction "3_3") (pintype "passive"))
      (node (ref "U1") (pin "37") (pinfunction "PA14-JTCK-SWCLK_37") (pintype "bidirectional"))
    )
    (net (code "54") (name "SWDIO") (class "Default")
      (node (ref "J3") (pin "2") (pinfunction "2_2") (pintype "passive"))
      (node (ref "U1") (pin "34") (pinfunction "PA13-JTMS-SWDIO_34") (pintype "bidirectional"))
    )
    (net (code "55") (name "USART_RX") (class "Default")
      (node (ref "J7") (pin "3") (pinfunction "3_3") (pintype "bidirectional"))
      (node (ref "U1") (pin "43") (pinfunction "PB7_43") (pintype "bidirectional"))
    )
    (net (code "56") (name "USART_TX") (class "Default")
      (node (ref "J7") (pin "2") (pinfunction "2_2") (pintype "bidirectional"))
      (node (ref "U1") (pin "42") (pinfunction "PB6_42") (pintype "bidirectional"))
    )
    (net (code "57") (name "USB_DM") (class "Default")
      (node (ref "J2") (pin "A7") (pinfunction "DN1_A7") (pintype "passive"))
      (node (ref "J2") (pin "B7") (pinfunction "DN2_B7") (pintype "passive"))
      (node (ref "U1") (pin "32") (pinfunction "PA11_32") (pintype "bidirectional"))
    )
    (net (code "58") (name "USB_DP") (class "Default")
      (node (ref "J2") (pin "A6") (pinfunction "DP1_A6") (pintype "passive"))
      (node (ref "J2") (pin "B6") (pinfunction "DP2_B6") (pintype "passive"))
      (node (ref "R5") (pin "2") (pinfunction "2_2") (pintype "passive"))
      (node (ref "U1") (pin "33") (pinfunction "PA12_33") (pintype "bidirectional"))
    )
    (net (code "59") (name "unconnected-(IC5-ENA-Pad5)") (class "Default")
      (node (ref "IC5") (pin "5") (pinfunction "ENA_5") (pintype "bidirectional"))
    )
    (net (code "60") (name "unconnected-(IC5-NC_1-Pad2)") (class "Default")
      (node (ref "IC5") (pin "2") (pinfunction "NC_1_2") (pintype "bidirectional"))
    )
    (net (code "61") (name "unconnected-(IC5-NC_2-Pad3)") (class "Default")
      (node (ref "IC5") (pin "3") (pinfunction "NC_2_3") (pintype "bidirectional"))
    )
    (net (code "62") (name "unconnected-(J2-SBU1-PadA8)") (class "Default")
      (node (ref "J2") (pin "A8") (pinfunction "SBU1_A8") (pintype "passive"))
    )
    (net (code "63") (name "unconnected-(J2-SBU2-PadB8)") (class "Default")
      (node (ref "J2") (pin "B8") (pinfunction "SBU2_B8") (pintype "passive"))
    )
    (net (code "64") (name "unconnected-(U1-PA7-Pad17)") (class "Default")
      (node (ref "U1") (pin "17") (pinfunction "PA7_17") (pintype "bidirectional"))
    )
    (net (code "65") (name "unconnected-(U1-PA15-JTDI-Pad38)") (class "Default")
      (node (ref "U1") (pin "38") (pinfunction "PA15-JTDI_38") (pintype "bidirectional"))
    )
    (net (code "66") (name "unconnected-(U1-PB0-Pad18)") (class "Default")
      (node (ref "U1") (pin "18") (pinfunction "PB0_18") (pintype "bidirectional"))
    )
    (net (code "67") (name "unconnected-(U1-PB1-Pad19)") (class "Default")
      (node (ref "U1") (pin "19") (pinfunction "PB1_19") (pintype "bidirectional"))
    )
    (net (code "68") (name "unconnected-(U1-PB2-Pad20)") (class "Default")
      (node (ref "U1") (pin "20") (pinfunction "PB2_20") (pintype "bidirectional"))
    )
    (net (code "69") (name "unconnected-(U1-PB10-Pad21)") (class "Default")
      (node (ref "U1") (pin "21") (pinfunction "PB10_21") (pintype "bidirectional"))
    )
    (net (code "70") (name "unconnected-(U1-PB11-Pad22)") (class "Default")
      (node (ref "U1") (pin "22") (pinfunction "PB11_22") (pintype "bidirectional"))
    )
    (net (code "71") (name "unconnected-(U1-PB12-Pad25)") (class "Default")
      (node (ref "U1") (pin "25") (pinfunction "PB12_25") (pintype "bidirectional"))
    )
    (net (code "72") (name "unconnected-(U1-VBAT-Pad1)") (class "Default")
      (node (ref "U1") (pin "1") (pinfunction "VBAT_1") (pintype "passive"))
    )
    (net (code "73") (name "~{EMS}") (class "Default")
      (node (ref "J12") (pin "2") (pinfunction "2_2") (pintype "bidirectional"))
      (node (ref "J15") (pin "2") (pinfunction "2_2") (pintype "bidirectional"))
      (node (ref "R3") (pin "1") (pinfunction "1_1") (pintype "passive"))
      (node (ref "U1") (pin "13") (pinfunction "PA3_13") (pintype "bidirectional"))
      (node (ref "U2") (pin "3") (pinfunction "EMIT_3") (pintype "passive"))
    )
    (net (code "74") (name "~{RESET}") (class "Default")
      (node (ref "C14") (pin "2") (pinfunction "2_2") (pintype "passive"))
      (node (ref "S1") (pin "P$2") (pinfunction "2_P$2") (pintype "bidirectional"))
      (node (ref "U1") (pin "7") (pinfunction "NRST_7") (pintype "bidirectional"))
    )
  )
)
